# main_SM.net
KiCad netlist of a schematic drawn in EAGLE
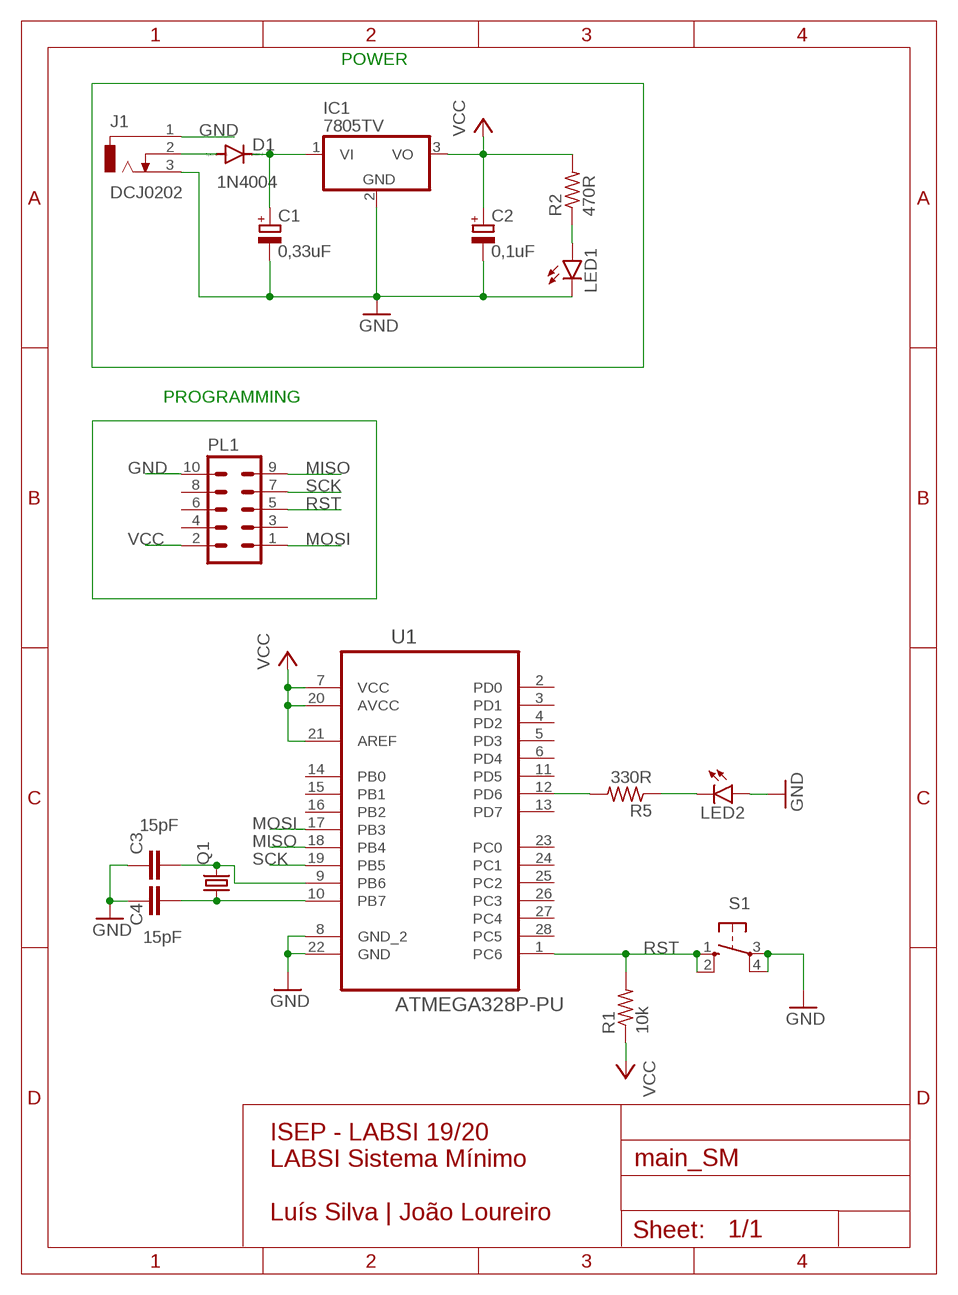
[diagram p0: schematic, sheet 1]

(export (version "E")
  (design (tool "Eeschema 10.0.6"))
  (components
    (comp (ref "C1")
      (value "0,33uF")
      (footprint "eagle-import:B45181A")
      (libsource (lib "eagle-import") (part "CPOL-EUB45181A"))
    )
    (comp (ref "C2")
      (value "0,1uF")
      (footprint "eagle-import:B45181A")
      (libsource (lib "eagle-import") (part "CPOL-EUB45181A"))
    )
    (comp (ref "C3")
      (value "15pF")
      (footprint "eagle-import:C5B3")
      (libsource (lib "eagle-import") (part "C5/3"))
    )
    (comp (ref "C4")
      (value "15pF")
      (footprint "eagle-import:C5B3")
      (libsource (lib "eagle-import") (part "C5/3"))
    )
    (comp (ref "D1")
      (value "1N4004")
      (footprint "eagle-import:DO41-10")
      (libsource (lib "eagle-import") (part "1N4004"))
    )
    (comp (ref "IC1")
      (value "7805TV")
      (footprint "eagle-import:TO220V")
      (libsource (lib "eagle-import") (part "78TV05"))
    )
    (comp (ref "J1")
      (value "DCJ0202")
      (footprint "eagle-import:DCJ0202")
      (libsource (lib "eagle-import") (part "DCJ0202"))
    )
    (comp (ref "LED1")
      (value "LED3MM")
      (footprint "eagle-import:LED3MM")
      (libsource (lib "eagle-import") (part "LED3MM"))
    )
    (comp (ref "LED2")
      (value "LED3MM")
      (footprint "eagle-import:LED3MM")
      (libsource (lib "eagle-import") (part "LED3MM"))
    )
    (comp (ref "PL1")
      (value "10H")
      (footprint "eagle-import:10H")
      (libsource (lib "eagle-import") (part "10H"))
    )
    (comp (ref "Q1")
      (value "CRYSTALHC49S")
      (footprint "eagle-import:HC49_S")
      (libsource (lib "eagle-import") (part "CRYSTALHC49S"))
    )
    (comp (ref "R1")
      (value "10k")
      (footprint "eagle-import:0207_10")
      (libsource (lib "eagle-import") (part "R-US_0207/10"))
    )
    (comp (ref "R2")
      (value "470R")
      (footprint "eagle-import:0207_10")
      (libsource (lib "eagle-import") (part "R-US_0207/10"))
    )
    (comp (ref "R5")
      (value "330R")
      (footprint "eagle-import:0207_10")
      (libsource (lib "eagle-import") (part "R-US_0207/10"))
    )
    (comp (ref "S1")
      (value "10-XX")
      (footprint "eagle-import:B3F-10XX")
      (fields (field (name "MPN") "B3F-1000"))
      (libsource (lib "eagle-import") (part "10-XX"))
    )
    (comp (ref "U1")
      (value "ATMEGA328P-PU")
      (footprint "eagle-import:DIP254P762X457-28")
      (fields (field (name "MF") "Generic"))
      (libsource (lib "eagle-import") (part "ATMEGA328P-PU"))
    )
  )
  (nets
    (net (code "1") (name "/MISO") (class "Default")
      (node (ref "PL1") (pin "9") (pinfunction "9_9") (pintype "passive"))
      (node (ref "U1") (pin "18") (pinfunction "PB4_18") (pintype "bidirectional"))
    )
    (net (code "2") (name "/MOSI") (class "Default")
      (node (ref "PL1") (pin "1") (pinfunction "1_1") (pintype "passive"))
      (node (ref "U1") (pin "17") (pinfunction "PB3_17") (pintype "bidirectional"))
    )
    (net (code "3") (name "/RST") (class "Default")
      (node (ref "PL1") (pin "5") (pinfunction "5_5") (pintype "passive"))
      (node (ref "R1") (pin "2") (pinfunction "2_2") (pintype "passive"))
      (node (ref "S1") (pin "1") (pinfunction "S_1") (pintype "passive"))
      (node (ref "S1") (pin "2") (pinfunction "S1_2") (pintype "passive"))
      (node (ref "U1") (pin "1") (pinfunction "PC6_1") (pintype "bidirectional"))
    )
    (net (code "4") (name "/SCK") (class "Default")
      (node (ref "PL1") (pin "7") (pinfunction "7_7") (pintype "passive"))
      (node (ref "U1") (pin "19") (pinfunction "PB5_19") (pintype "bidirectional"))
    )
    (net (code "5") (name "GND") (class "Default")
      (node (ref "C1") (pin "-") (pinfunction "-_-") (pintype "passive"))
      (node (ref "C2") (pin "-") (pinfunction "-_-") (pintype "passive"))
      (node (ref "C3") (pin "1") (pinfunction "1_1") (pintype "passive"))
      (node (ref "C4") (pin "1") (pinfunction "1_1") (pintype "passive"))
      (node (ref "IC1") (pin "2") (pinfunction "GND_2") (pintype "passive"))
      (node (ref "J1") (pin "1") (pinfunction "1_1") (pintype "passive"))
      (node (ref "J1") (pin "3") (pinfunction "3_3") (pintype "passive"))
      (node (ref "LED1") (pin "K") (pinfunction "C_K") (pintype "passive"))
      (node (ref "LED2") (pin "A") (pinfunction "A_A") (pintype "passive"))
      (node (ref "PL1") (pin "10") (pinfunction "10_10") (pintype "passive"))
      (node (ref "S1") (pin "3") (pinfunction "P_3") (pintype "passive"))
      (node (ref "S1") (pin "4") (pinfunction "P1_4") (pintype "passive"))
      (node (ref "U1") (pin "22") (pinfunction "GND_22") (pintype "passive"))
      (node (ref "U1") (pin "8") (pinfunction "GND_2_8") (pintype "passive"))
    )
    (net (code "6") (name "Net-(D1-PadA)") (class "Default")
      (node (ref "D1") (pin "A") (pinfunction "A_A") (pintype "passive"))
      (node (ref "J1") (pin "2") (pinfunction "2_2") (pintype "passive"))
    )
    (net (code "7") (name "Net-(IC1-VI)") (class "Default")
      (node (ref "C1") (pin "+") (pinfunction "+_+") (pintype "passive"))
      (node (ref "D1") (pin "C") (pinfunction "C_C") (pintype "passive"))
      (node (ref "IC1") (pin "1") (pinfunction "VI_1") (pintype "input"))
    )
    (net (code "8") (name "Net-(LED1-PadA)") (class "Default")
      (node (ref "LED1") (pin "A") (pinfunction "A_A") (pintype "passive"))
      (node (ref "R2") (pin "1") (pinfunction "1_1") (pintype "passive"))
    )
    (net (code "9") (name "Net-(LED2-C)") (class "Default")
      (node (ref "LED2") (pin "K") (pinfunction "C_K") (pintype "passive"))
      (node (ref "R5") (pin "1") (pinfunction "1_1") (pintype "passive"))
    )
    (net (code "10") (name "Net-(U1-PB6)") (class "Default")
      (node (ref "C3") (pin "2") (pinfunction "2_2") (pintype "passive"))
      (node (ref "Q1") (pin "2") (pinfunction "2_2") (pintype "passive"))
      (node (ref "U1") (pin "9") (pinfunction "PB6_9") (pintype "bidirectional"))
    )
    (net (code "11") (name "Net-(U1-PB7)") (class "Default")
      (node (ref "C4") (pin "2") (pinfunction "2_2") (pintype "passive"))
      (node (ref "Q1") (pin "1") (pinfunction "1_1") (pintype "passive"))
      (node (ref "U1") (pin "10") (pinfunction "PB7_10") (pintype "bidirectional"))
    )
    (net (code "12") (name "Net-(U1-PD6)") (class "Default")
      (node (ref "R5") (pin "2") (pinfunction "2_2") (pintype "passive"))
      (node (ref "U1") (pin "12") (pinfunction "PD6_12") (pintype "bidirectional"))
    )
    (net (code "13") (name "VCC") (class "Default")
      (node (ref "C2") (pin "+") (pinfunction "+_+") (pintype "passive"))
      (node (ref "IC1") (pin "3") (pinfunction "VO_3") (pintype "passive"))
      (node (ref "PL1") (pin "2") (pinfunction "2_2") (pintype "passive"))
      (node (ref "R1") (pin "1") (pinfunction "1_1") (pintype "passive"))
      (node (ref "R2") (pin "2") (pinfunction "2_2") (pintype "passive"))
      (node (ref "U1") (pin "20") (pinfunction "AVCC_20") (pintype "power_in"))
      (node (ref "U1") (pin "21") (pinfunction "AREF_21") (pintype "input"))
      (node (ref "U1") (pin "7") (pinfunction "VCC_7") (pintype "power_in"))
    )
    (net (code "14") (name "unconnected-(PL1-Pad3)") (class "Default")
      (node (ref "PL1") (pin "3") (pinfunction "3_3") (pintype "passive"))
    )
    (net (code "15") (name "unconnected-(PL1-Pad4)") (class "Default")
      (node (ref "PL1") (pin "4") (pinfunction "4_4") (pintype "passive"))
    )
    (net (code "16") (name "unconnected-(PL1-Pad6)") (class "Default")
      (node (ref "PL1") (pin "6") (pinfunction "6_6") (pintype "passive"))
    )
    (net (code "17") (name "unconnected-(PL1-Pad8)") (class "Default")
      (node (ref "PL1") (pin "8") (pinfunction "8_8") (pintype "passive"))
    )
    (net (code "18") (name "unconnected-(U1-PB0-Pad14)") (class "Default")
      (node (ref "U1") (pin "14") (pinfunction "PB0_14") (pintype "bidirectional"))
    )
    (net (code "19") (name "unconnected-(U1-PB1-Pad15)") (class "Default")
      (node (ref "U1") (pin "15") (pinfunction "PB1_15") (pintype "bidirectional"))
    )
    (net (code "20") (name "unconnected-(U1-PB2-Pad16)") (class "Default")
      (node (ref "U1") (pin "16") (pinfunction "PB2_16") (pintype "bidirectional"))
    )
    (net (code "21") (name "unconnected-(U1-PC0-Pad23)") (class "Default")
      (node (ref "U1") (pin "23") (pinfunction "PC0_23") (pintype "bidirectional"))
    )
    (net (code "22") (name "unconnected-(U1-PC1-Pad24)") (class "Default")
      (node (ref "U1") (pin "24") (pinfunction "PC1_24") (pintype "bidirectional"))
    )
    (net (code "23") (name "unconnected-(U1-PC2-Pad25)") (class "Default")
      (node (ref "U1") (pin "25") (pinfunction "PC2_25") (pintype "bidirectional"))
    )
    (net (code "24") (name "unconnected-(U1-PC3-Pad26)") (class "Default")
      (node (ref "U1") (pin "26") (pinfunction "PC3_26") (pintype "bidirectional"))
    )
    (net (code "25") (name "unconnected-(U1-PC4-Pad27)") (class "Default")
      (node (ref "U1") (pin "27") (pinfunction "PC4_27") (pintype "bidirectional"))
    )
    (net (code "26") (name "unconnected-(U1-PC5-Pad28)") (class "Default")
      (node (ref "U1") (pin "28") (pinfunction "PC5_28") (pintype "bidirectional"))
    )
    (net (code "27") (name "unconnected-(U1-PD0-Pad2)") (class "Default")
      (node (ref "U1") (pin "2") (pinfunction "PD0_2") (pintype "bidirectional"))
    )
    (net (code "28") (name "unconnected-(U1-PD1-Pad3)") (class "Default")
      (node (ref "U1") (pin "3") (pinfunction "PD1_3") (pintype "bidirectional"))
    )
    (net (code "29") (name "unconnected-(U1-PD2-Pad4)") (class "Default")
      (node (ref "U1") (pin "4") (pinfunction "PD2_4") (pintype "bidirectional"))
    )
    (net (code "30") (name "unconnected-(U1-PD3-Pad5)") (class "Default")
      (node (ref "U1") (pin "5") (pinfunction "PD3_5") (pintype "bidirectional"))
    )
    (net (code "31") (name "unconnected-(U1-PD4-Pad6)") (class "Default")
      (node (ref "U1") (pin "6") (pinfunction "PD4_6") (pintype "bidirectional"))
    )
    (net (code "32") (name "unconnected-(U1-PD5-Pad11)") (class "Default")
      (node (ref "U1") (pin "11") (pinfunction "PD5_11") (pintype "bidirectional"))
    )
    (net (code "33") (name "unconnected-(U1-PD7-Pad13)") (class "Default")
      (node (ref "U1") (pin "13") (pinfunction "PD7_13") (pintype "bidirectional"))
    )
  )
)
